# Eletromiografia.net
KiCad netlist of a schematic drawn in EAGLE
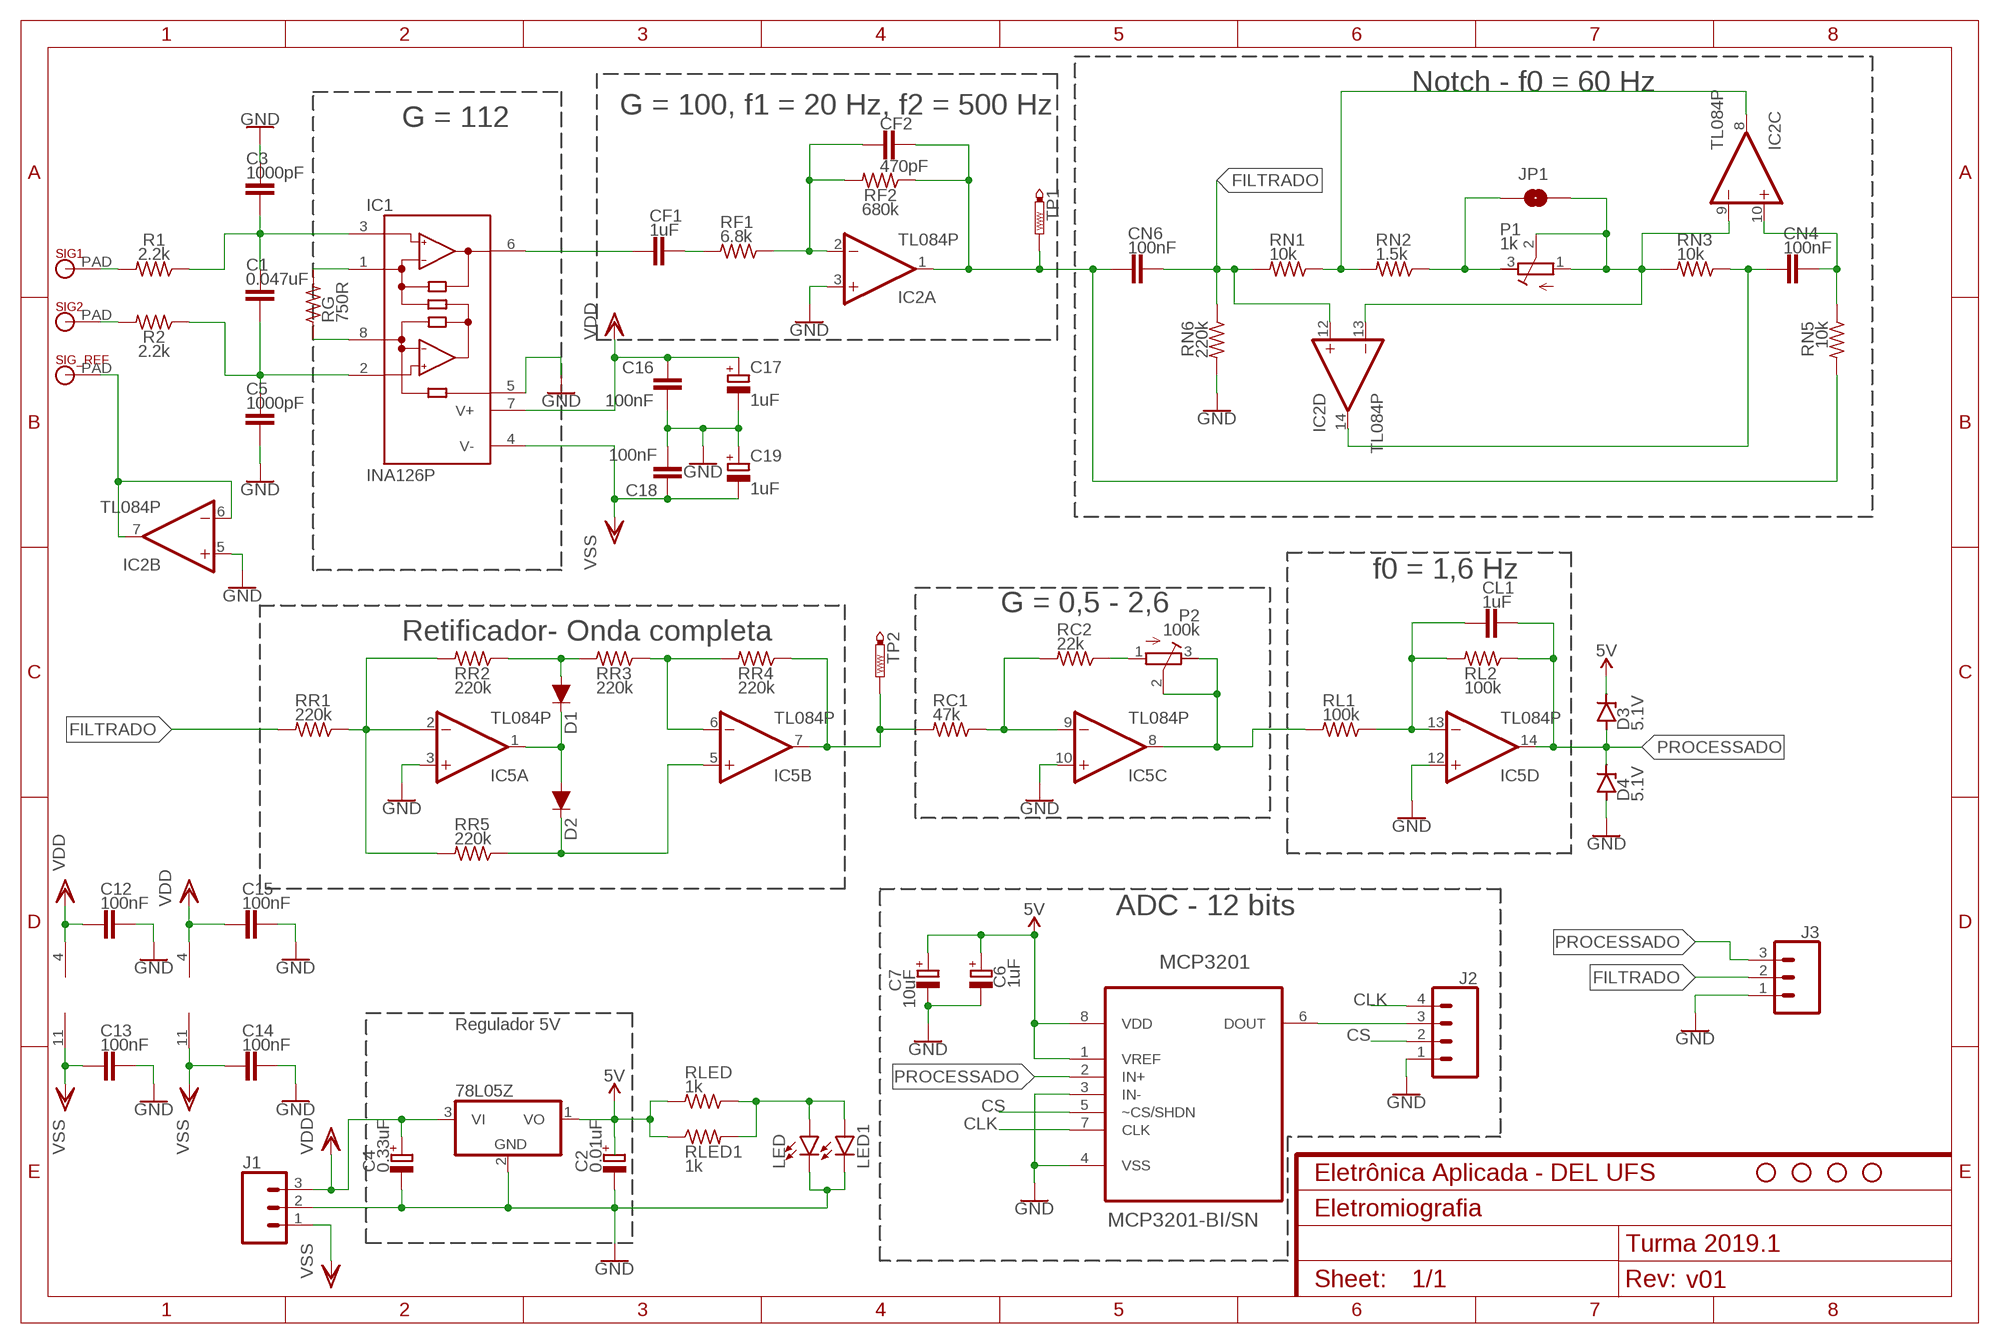
[diagram p0: schematic, sheet 1]

(export (version "E")
  (design (tool "Eeschema 10.0.6"))
  (components
    (comp (ref "C1")
      (value "0.047uF")
      (footprint "eagle-import:C025-025X050")
      (libsource (lib "eagle-import") (part "C-EU025-025X050"))
    )
    (comp (ref "C2")
      (value "0.01uF")
      (footprint "eagle-import:E2,5-6")
      (libsource (lib "eagle-import") (part "CPOL-EUE2.5-6"))
    )
    (comp (ref "C3")
      (value "1000pF")
      (footprint "eagle-import:C025-025X050")
      (libsource (lib "eagle-import") (part "C-EU025-025X050"))
    )
    (comp (ref "C4")
      (value "0.33uF")
      (footprint "eagle-import:E2,5-6")
      (libsource (lib "eagle-import") (part "CPOL-EUE2.5-6"))
    )
    (comp (ref "C5")
      (value "1000pF")
      (footprint "eagle-import:C025-025X050")
      (libsource (lib "eagle-import") (part "C-EU025-025X050"))
    )
    (comp (ref "C6")
      (value "1uF")
      (footprint "eagle-import:E2,5-6")
      (libsource (lib "eagle-import") (part "CPOL-EUE2.5-6"))
    )
    (comp (ref "C7")
      (value "10uF")
      (footprint "eagle-import:E2,5-6")
      (libsource (lib "eagle-import") (part "CPOL-EUE2.5-6"))
    )
    (comp (ref "C12")
      (value "100nF")
      (footprint "eagle-import:C025-025X050")
      (libsource (lib "eagle-import") (part "C-EU025-025X050"))
    )
    (comp (ref "C13")
      (value "100nF")
      (footprint "eagle-import:C025-025X050")
      (libsource (lib "eagle-import") (part "C-EU025-025X050"))
    )
    (comp (ref "C14")
      (value "100nF")
      (footprint "eagle-import:C025-025X050")
      (libsource (lib "eagle-import") (part "C-EU025-025X050"))
    )
    (comp (ref "C15")
      (value "100nF")
      (footprint "eagle-import:C025-025X050")
      (libsource (lib "eagle-import") (part "C-EU025-025X050"))
    )
    (comp (ref "C16")
      (value "100nF")
      (footprint "eagle-import:C025-025X050")
      (libsource (lib "eagle-import") (part "C-EU025-025X050"))
    )
    (comp (ref "C17")
      (value "1uF")
      (footprint "eagle-import:E2,5-6")
      (libsource (lib "eagle-import") (part "CPOL-EUE2.5-6"))
    )
    (comp (ref "C18")
      (value "100nF")
      (footprint "eagle-import:C025-025X050")
      (libsource (lib "eagle-import") (part "C-EU025-025X050"))
    )
    (comp (ref "C19")
      (value "1uF")
      (footprint "eagle-import:E2,5-6")
      (libsource (lib "eagle-import") (part "CPOL-EUE2.5-6"))
    )
    (comp (ref "CF1")
      (value "1uF")
      (footprint "eagle-import:C025-025X050")
      (libsource (lib "eagle-import") (part "C-EU025-025X050"))
    )
    (comp (ref "CF2")
      (value "470pF")
      (footprint "eagle-import:C025-025X050")
      (libsource (lib "eagle-import") (part "C-EU025-025X050"))
    )
    (comp (ref "CL1")
      (value "1uF")
      (footprint "eagle-import:C025-025X050")
      (libsource (lib "eagle-import") (part "C-EU025-025X050"))
    )
    (comp (ref "CN4")
      (value "100nF")
      (footprint "eagle-import:C025-025X050")
      (libsource (lib "eagle-import") (part "C-EU025-025X050"))
    )
    (comp (ref "CN6")
      (value "100nF")
      (footprint "eagle-import:C025-025X050")
      (libsource (lib "eagle-import") (part "C-EU025-025X050"))
    )
    (comp (ref "D1")
      (value "200mA/100V/1V")
      (footprint "eagle-import:DIODE-1N4148")
      (libsource (lib "eagle-import") (part "DIODE-1N4148"))
    )
    (comp (ref "D2")
      (value "200mA/100V/1V")
      (footprint "eagle-import:DIODE-1N4148")
      (libsource (lib "eagle-import") (part "DIODE-1N4148"))
    )
    (comp (ref "D3")
      (value "5.1V")
      (footprint "eagle-import:ZDIO-7.5")
      (libsource (lib "eagle-import") (part "ZENER-DIODEZD-7.5"))
    )
    (comp (ref "D4")
      (value "5.1V")
      (footprint "eagle-import:ZDIO-7.5")
      (libsource (lib "eagle-import") (part "ZENER-DIODEZD-7.5"))
    )
    (comp (ref "H1")
      (value "STAND-OFFTIGHT")
      (footprint "eagle-import:STAND-OFF-TIGHT")
      (libsource (lib "eagle-import") (part "STAND-OFFTIGHT"))
    )
    (comp (ref "H2")
      (value "STAND-OFFTIGHT")
      (footprint "eagle-import:STAND-OFF-TIGHT")
      (libsource (lib "eagle-import") (part "STAND-OFFTIGHT"))
    )
    (comp (ref "H3")
      (value "STAND-OFFTIGHT")
      (footprint "eagle-import:STAND-OFF-TIGHT")
      (libsource (lib "eagle-import") (part "STAND-OFFTIGHT"))
    )
    (comp (ref "H4")
      (value "STAND-OFFTIGHT")
      (footprint "eagle-import:STAND-OFF-TIGHT")
      (libsource (lib "eagle-import") (part "STAND-OFFTIGHT"))
    )
    (comp (ref "IC1")
      (value "INA126P")
      (footprint "eagle-import:DIL08")
      (fields (field (name "MF") "TEXAS INSTRUMENT CONNECTORS"))
      (libsource (lib "eagle-import") (part "INA126P"))
    )
    (comp (ref "IC2")
      (value "TL084P")
      (footprint "eagle-import:DIL14")
      (libsource (lib "eagle-import") (part "TL084P"))
    )
    (comp (ref "IC3")
      (value "78L05Z")
      (footprint "eagle-import:TO92")
      (libsource (lib "eagle-import") (part "78ZL05"))
    )
    (comp (ref "IC5")
      (value "TL084P")
      (footprint "eagle-import:DIL14")
      (libsource (lib "eagle-import") (part "TL084P"))
    )
    (comp (ref "J1")
      (value "CONN_03LONGPADS")
      (footprint "eagle-import:1X03_LONGPADS")
      (libsource (lib "eagle-import") (part "CONN_03LONGPADS"))
    )
    (comp (ref "J2")
      (value "CONN_041X04_NO_SILK")
      (footprint "eagle-import:1X04_NO_SILK")
      (libsource (lib "eagle-import") (part "CONN_041X04_NO_SILK"))
    )
    (comp (ref "J3")
      (value "CONN_031X03_NO_SILK")
      (footprint "eagle-import:1X03_NO_SILK")
      (libsource (lib "eagle-import") (part "CONN_031X03_NO_SILK"))
    )
    (comp (ref "JP1")
      (value "JUMPER-SMT_2_NO_NO-SILK_ROUND")
      (footprint "eagle-import:SMT-JUMPER_2_NO_NO-SILK_ROUND")
      (libsource (lib "eagle-import") (part "JUMPER-SMT_2_NO_NO-SILK_ROUND"))
    )
    (comp (ref "LED")
      (value "LED3MM")
      (footprint "eagle-import:LED_3MM")
      (libsource (lib "eagle-import") (part "LED3MM"))
    )
    (comp (ref "LED1")
      (value "LEDCHIP-LED0805")
      (footprint "eagle-import:CHIP-LED0805")
      (libsource (lib "eagle-import") (part "LEDCHIP-LED0805"))
    )
    (comp (ref "MCP3201")
      (value "MCP3201-BI/SN")
      (footprint "eagle-import:SOIC127P600X175-8N")
      (fields (field (name "MF") "Microchip"))
      (libsource (lib "eagle-import") (part "MCP3201-BI/SN"))
    )
    (comp (ref "P1")
      (value "1k")
      (footprint "eagle-import:RTRIM64W")
      (libsource (lib "eagle-import") (part "R-TRIMM64W"))
    )
    (comp (ref "P2")
      (value "100k")
      (footprint "eagle-import:RTRIM64W")
      (libsource (lib "eagle-import") (part "R-TRIMM64W"))
    )
    (comp (ref "R1")
      (value "2.2k")
      (footprint "eagle-import:0207_10")
      (libsource (lib "eagle-import") (part "R-US_0207/10"))
    )
    (comp (ref "R2")
      (value "2.2k")
      (footprint "eagle-import:0207_10")
      (libsource (lib "eagle-import") (part "R-US_0207/10"))
    )
    (comp (ref "RC1")
      (value "47k")
      (footprint "eagle-import:0207_10")
      (libsource (lib "eagle-import") (part "R-US_0207/10"))
    )
    (comp (ref "RC2")
      (value "22k")
      (footprint "eagle-import:0207_10")
      (libsource (lib "eagle-import") (part "R-US_0207/10"))
    )
    (comp (ref "RF1")
      (value "6.8k")
      (footprint "eagle-import:0207_10")
      (libsource (lib "eagle-import") (part "R-US_0207/10"))
    )
    (comp (ref "RF2")
      (value "680k")
      (footprint "eagle-import:0207_10")
      (libsource (lib "eagle-import") (part "R-US_0207/10"))
    )
    (comp (ref "RG")
      (value "750R")
      (footprint "eagle-import:0207_10")
      (libsource (lib "eagle-import") (part "R-US_0207/10"))
    )
    (comp (ref "RL1")
      (value "100k")
      (footprint "eagle-import:0207_10")
      (libsource (lib "eagle-import") (part "R-US_0207/10"))
    )
    (comp (ref "RL2")
      (value "100k")
      (footprint "eagle-import:0207_10")
      (libsource (lib "eagle-import") (part "R-US_0207/10"))
    )
    (comp (ref "RLED")
      (value "1k")
      (footprint "eagle-import:0207_10")
      (libsource (lib "eagle-import") (part "R-US_0207/10"))
    )
    (comp (ref "RLED1")
      (value "1k")
      (footprint "eagle-import:R0805")
      (libsource (lib "eagle-import") (part "R-US_R0805"))
    )
    (comp (ref "RN1")
      (value "10k")
      (footprint "eagle-import:0207_10")
      (libsource (lib "eagle-import") (part "R-US_0207/10"))
    )
    (comp (ref "RN2")
      (value "1.5k")
      (footprint "eagle-import:0207_10")
      (libsource (lib "eagle-import") (part "R-US_0207/10"))
    )
    (comp (ref "RN3")
      (value "10k")
      (footprint "eagle-import:0207_10")
      (libsource (lib "eagle-import") (part "R-US_0207/10"))
    )
    (comp (ref "RN5")
      (value "10k")
      (footprint "eagle-import:0207_10")
      (libsource (lib "eagle-import") (part "R-US_0207/10"))
    )
    (comp (ref "RN6")
      (value "220k")
      (footprint "eagle-import:0207_10")
      (libsource (lib "eagle-import") (part "R-US_0207/10"))
    )
    (comp (ref "RR1")
      (value "220k")
      (footprint "eagle-import:0207_10")
      (libsource (lib "eagle-import") (part "R-US_0207/10"))
    )
    (comp (ref "RR2")
      (value "220k")
      (footprint "eagle-import:0207_10")
      (libsource (lib "eagle-import") (part "R-US_0207/10"))
    )
    (comp (ref "RR3")
      (value "220k")
      (footprint "eagle-import:0207_10")
      (libsource (lib "eagle-import") (part "R-US_0207/10"))
    )
    (comp (ref "RR4")
      (value "220k")
      (footprint "eagle-import:0207_10")
      (libsource (lib "eagle-import") (part "R-US_0207/10"))
    )
    (comp (ref "RR5")
      (value "220k")
      (footprint "eagle-import:0207_10")
      (libsource (lib "eagle-import") (part "R-US_0207/10"))
    )
    (comp (ref "SIG1")
      (value "MICROBIT_PAD")
      (footprint "eagle-import:MICROBIT_PAD")
      (libsource (lib "eagle-import") (part "MICROBIT_PAD"))
    )
    (comp (ref "SIG2")
      (value "MICROBIT_PAD")
      (footprint "eagle-import:MICROBIT_PAD")
      (libsource (lib "eagle-import") (part "MICROBIT_PAD"))
    )
    (comp (ref "SIG_REF")
      (value "MICROBIT_PAD")
      (footprint "eagle-import:MICROBIT_PAD")
      (libsource (lib "eagle-import") (part "MICROBIT_PAD"))
    )
    (comp (ref "TP1")
      (value "PTR1B1,27")
      (footprint "eagle-import:B1,27")
      (libsource (lib "eagle-import") (part "PTR1B1,27"))
    )
    (comp (ref "TP2")
      (value "PTR1B1,27")
      (footprint "eagle-import:B1,27")
      (libsource (lib "eagle-import") (part "PTR1B1,27"))
    )
  )
  (nets
    (net (code "1") (name "/CLK") (class "Default")
      (node (ref "J2") (pin "4") (pinfunction "4_4") (pintype "passive"))
      (node (ref "MCP3201") (pin "7") (pinfunction "CLK_7") (pintype "input"))
    )
    (net (code "2") (name "/CS") (class "Default")
      (node (ref "J2") (pin "2") (pinfunction "2_2") (pintype "passive"))
      (node (ref "MCP3201") (pin "5") (pinfunction "~{CS/SHDN}_5") (pintype "input"))
    )
    (net (code "3") (name "5V") (class "Default")
      (node (ref "C2") (pin "+") (pinfunction "+_+") (pintype "passive"))
      (node (ref "C6") (pin "+") (pinfunction "+_+") (pintype "passive"))
      (node (ref "C7") (pin "+") (pinfunction "+_+") (pintype "passive"))
      (node (ref "D3") (pin "C") (pinfunction "C_C") (pintype "passive"))
      (node (ref "IC3") (pin "1") (pinfunction "VO_1") (pintype "passive"))
      (node (ref "MCP3201") (pin "1") (pinfunction "VREF_1") (pintype "input"))
      (node (ref "MCP3201") (pin "8") (pinfunction "VDD_8") (pintype "power_in"))
      (node (ref "RLED") (pin "2") (pinfunction "2_2") (pintype "passive"))
      (node (ref "RLED1") (pin "1") (pinfunction "1_1") (pintype "passive"))
    )
    (net (code "4") (name "FILTRADO") (class "Default")
      (node (ref "CN6") (pin "2") (pinfunction "2_2") (pintype "passive"))
      (node (ref "IC2") (pin "12") (pinfunction "+IN_12") (pintype "input"))
      (node (ref "J3") (pin "2") (pinfunction "2_2") (pintype "passive"))
      (node (ref "RN1") (pin "2") (pinfunction "2_2") (pintype "passive"))
      (node (ref "RN6") (pin "1") (pinfunction "1_1") (pintype "passive"))
      (node (ref "RR1") (pin "2") (pinfunction "2_2") (pintype "passive"))
    )
    (net (code "5") (name "GND") (class "Default")
      (node (ref "C12") (pin "2") (pinfunction "2_2") (pintype "passive"))
      (node (ref "C13") (pin "2") (pinfunction "2_2") (pintype "passive"))
      (node (ref "C14") (pin "2") (pinfunction "2_2") (pintype "passive"))
      (node (ref "C15") (pin "2") (pinfunction "2_2") (pintype "passive"))
      (node (ref "C16") (pin "1") (pinfunction "1_1") (pintype "passive"))
      (node (ref "C17") (pin "-") (pinfunction "-_-") (pintype "passive"))
      (node (ref "C18") (pin "2") (pinfunction "2_2") (pintype "passive"))
      (node (ref "C19") (pin "+") (pinfunction "+_+") (pintype "passive"))
      (node (ref "C2") (pin "-") (pinfunction "-_-") (pintype "passive"))
      (node (ref "C3") (pin "2") (pinfunction "2_2") (pintype "passive"))
      (node (ref "C4") (pin "-") (pinfunction "-_-") (pintype "passive"))
      (node (ref "C5") (pin "1") (pinfunction "1_1") (pintype "passive"))
      (node (ref "C6") (pin "-") (pinfunction "-_-") (pintype "passive"))
      (node (ref "C7") (pin "-") (pinfunction "-_-") (pintype "passive"))
      (node (ref "D4") (pin "A") (pinfunction "A_A") (pintype "passive"))
      (node (ref "IC1") (pin "5") (pinfunction "REF_5") (pintype "passive"))
      (node (ref "IC2") (pin "3") (pinfunction "+IN_3") (pintype "input"))
      (node (ref "IC2") (pin "5") (pinfunction "+IN_5") (pintype "input"))
      (node (ref "IC3") (pin "2") (pinfunction "GND_2") (pintype "passive"))
      (node (ref "IC5") (pin "10") (pinfunction "+IN_10") (pintype "input"))
      (node (ref "IC5") (pin "12") (pinfunction "+IN_12") (pintype "input"))
      (node (ref "IC5") (pin "3") (pinfunction "+IN_3") (pintype "input"))
      (node (ref "J1") (pin "2") (pinfunction "2_2") (pintype "passive"))
      (node (ref "J2") (pin "1") (pinfunction "1_1") (pintype "passive"))
      (node (ref "J3") (pin "1") (pinfunction "1_1") (pintype "passive"))
      (node (ref "LED") (pin "K") (pinfunction "C_K") (pintype "passive"))
      (node (ref "LED1") (pin "C") (pinfunction "C_C") (pintype "passive"))
      (node (ref "MCP3201") (pin "3") (pinfunction "IN-_3") (pintype "input"))
      (node (ref "MCP3201") (pin "4") (pinfunction "VSS_4") (pintype "power_in"))
      (node (ref "RN6") (pin "2") (pinfunction "2_2") (pintype "passive"))
    )
    (net (code "6") (name "Net-(CF1-Pad2)") (class "Default")
      (node (ref "CF1") (pin "2") (pinfunction "2_2") (pintype "passive"))
      (node (ref "RF1") (pin "2") (pinfunction "2_2") (pintype "passive"))
    )
    (net (code "7") (name "Net-(D1-PadA)") (class "Default")
      (node (ref "D1") (pin "A") (pinfunction "A_A") (pintype "passive"))
      (node (ref "RR2") (pin "1") (pinfunction "1_1") (pintype "passive"))
      (node (ref "RR3") (pin "2") (pinfunction "2_2") (pintype "passive"))
    )
    (net (code "8") (name "Net-(IC1-+IN)") (class "Default")
      (node (ref "C1") (pin "2") (pinfunction "2_2") (pintype "passive"))
      (node (ref "C3") (pin "1") (pinfunction "1_1") (pintype "passive"))
      (node (ref "IC1") (pin "3") (pinfunction "+IN_3") (pintype "input"))
      (node (ref "R1") (pin "1") (pinfunction "1_1") (pintype "passive"))
    )
    (net (code "9") (name "Net-(IC1--IN)") (class "Default")
      (node (ref "C1") (pin "1") (pinfunction "1_1") (pintype "passive"))
      (node (ref "C5") (pin "2") (pinfunction "2_2") (pintype "passive"))
      (node (ref "IC1") (pin "2") (pinfunction "-IN_2") (pintype "input"))
      (node (ref "R2") (pin "1") (pinfunction "1_1") (pintype "passive"))
    )
    (net (code "10") (name "Net-(IC1-OUT)") (class "Default")
      (node (ref "CF1") (pin "1") (pinfunction "1_1") (pintype "passive"))
      (node (ref "IC1") (pin "6") (pinfunction "OUT_6") (pintype "output"))
    )
    (net (code "11") (name "Net-(IC1-RG-Pad1)") (class "Default")
      (node (ref "IC1") (pin "1") (pinfunction "RG_1") (pintype "passive"))
      (node (ref "RG") (pin "2") (pinfunction "2_2") (pintype "passive"))
    )
    (net (code "12") (name "Net-(IC1-RG-Pad8)") (class "Default")
      (node (ref "IC1") (pin "8") (pinfunction "RG_8") (pintype "passive"))
      (node (ref "RG") (pin "1") (pinfunction "1_1") (pintype "passive"))
    )
    (net (code "13") (name "Net-(IC2A--IN)") (class "Default")
      (node (ref "CF2") (pin "1") (pinfunction "1_1") (pintype "passive"))
      (node (ref "IC2") (pin "2") (pinfunction "-IN_2") (pintype "input"))
      (node (ref "RF1") (pin "1") (pinfunction "1_1") (pintype "passive"))
      (node (ref "RF2") (pin "2") (pinfunction "2_2") (pintype "passive"))
    )
    (net (code "14") (name "Net-(IC2A-OUT)") (class "Default")
      (node (ref "CF2") (pin "2") (pinfunction "2_2") (pintype "passive"))
      (node (ref "CN6") (pin "1") (pinfunction "1_1") (pintype "passive"))
      (node (ref "IC2") (pin "1") (pinfunction "OUT_1") (pintype "output"))
      (node (ref "RF2") (pin "1") (pinfunction "1_1") (pintype "passive"))
      (node (ref "RN5") (pin "2") (pinfunction "2_2") (pintype "passive"))
      (node (ref "TP1") (pin "TP") (pinfunction "TP_TP") (pintype "input"))
    )
    (net (code "15") (name "Net-(IC2B--IN)") (class "Default")
      (node (ref "IC2") (pin "6") (pinfunction "-IN_6") (pintype "input"))
      (node (ref "IC2") (pin "7") (pinfunction "OUT_7") (pintype "output"))
      (node (ref "SIG_REF") (pin "PAD") (pinfunction "P$1_PAD") (pintype "bidirectional"))
    )
    (net (code "16") (name "Net-(IC2C-+IN)") (class "Default")
      (node (ref "CN4") (pin "2") (pinfunction "2_2") (pintype "passive"))
      (node (ref "IC2") (pin "10") (pinfunction "+IN_10") (pintype "input"))
      (node (ref "RN5") (pin "1") (pinfunction "1_1") (pintype "passive"))
    )
    (net (code "17") (name "Net-(IC2C--IN)") (class "Default")
      (node (ref "IC2") (pin "13") (pinfunction "-IN_13") (pintype "input"))
      (node (ref "IC2") (pin "9") (pinfunction "-IN_9") (pintype "input"))
      (node (ref "JP1") (pin "2") (pinfunction "2_2") (pintype "passive"))
      (node (ref "P1") (pin "1") (pinfunction "A_1") (pintype "passive"))
      (node (ref "P1") (pin "2") (pinfunction "S_2") (pintype "passive"))
      (node (ref "RN3") (pin "2") (pinfunction "2_2") (pintype "passive"))
    )
    (net (code "18") (name "Net-(IC2C-OUT)") (class "Default")
      (node (ref "IC2") (pin "8") (pinfunction "OUT_8") (pintype "output"))
      (node (ref "RN1") (pin "1") (pinfunction "1_1") (pintype "passive"))
      (node (ref "RN2") (pin "2") (pinfunction "2_2") (pintype "passive"))
    )
    (net (code "19") (name "Net-(IC2D-OUT)") (class "Default")
      (node (ref "CN4") (pin "1") (pinfunction "1_1") (pintype "passive"))
      (node (ref "IC2") (pin "14") (pinfunction "OUT_14") (pintype "output"))
      (node (ref "RN3") (pin "1") (pinfunction "1_1") (pintype "passive"))
    )
    (net (code "20") (name "Net-(IC5A--IN)") (class "Default")
      (node (ref "IC5") (pin "2") (pinfunction "-IN_2") (pintype "input"))
      (node (ref "RR1") (pin "1") (pinfunction "1_1") (pintype "passive"))
      (node (ref "RR2") (pin "2") (pinfunction "2_2") (pintype "passive"))
      (node (ref "RR5") (pin "2") (pinfunction "2_2") (pintype "passive"))
    )
    (net (code "21") (name "Net-(IC5A-OUT)") (class "Default")
      (node (ref "D1") (pin "C") (pinfunction "C_C") (pintype "passive"))
      (node (ref "D2") (pin "A") (pinfunction "A_A") (pintype "passive"))
      (node (ref "IC5") (pin "1") (pinfunction "OUT_1") (pintype "output"))
    )
    (net (code "22") (name "Net-(IC5B-+IN)") (class "Default")
      (node (ref "D2") (pin "C") (pinfunction "C_C") (pintype "passive"))
      (node (ref "IC5") (pin "5") (pinfunction "+IN_5") (pintype "input"))
      (node (ref "RR5") (pin "1") (pinfunction "1_1") (pintype "passive"))
    )
    (net (code "23") (name "Net-(IC5B--IN)") (class "Default")
      (node (ref "IC5") (pin "6") (pinfunction "-IN_6") (pintype "input"))
      (node (ref "RR3") (pin "1") (pinfunction "1_1") (pintype "passive"))
      (node (ref "RR4") (pin "2") (pinfunction "2_2") (pintype "passive"))
    )
    (net (code "24") (name "Net-(IC5B-OUT)") (class "Default")
      (node (ref "IC5") (pin "7") (pinfunction "OUT_7") (pintype "output"))
      (node (ref "RC1") (pin "2") (pinfunction "2_2") (pintype "passive"))
      (node (ref "RR4") (pin "1") (pinfunction "1_1") (pintype "passive"))
      (node (ref "TP2") (pin "TP") (pinfunction "TP_TP") (pintype "input"))
    )
    (net (code "25") (name "Net-(IC5C--IN)") (class "Default")
      (node (ref "IC5") (pin "9") (pinfunction "-IN_9") (pintype "input"))
      (node (ref "RC1") (pin "1") (pinfunction "1_1") (pintype "passive"))
      (node (ref "RC2") (pin "2") (pinfunction "2_2") (pintype "passive"))
    )
    (net (code "26") (name "Net-(IC5C-OUT)") (class "Default")
      (node (ref "IC5") (pin "8") (pinfunction "OUT_8") (pintype "output"))
      (node (ref "P2") (pin "2") (pinfunction "S_2") (pintype "passive"))
      (node (ref "P2") (pin "3") (pinfunction "E_3") (pintype "passive"))
      (node (ref "RL1") (pin "2") (pinfunction "2_2") (pintype "passive"))
    )
    (net (code "27") (name "Net-(IC5D--IN)") (class "Default")
      (node (ref "CL1") (pin "1") (pinfunction "1_1") (pintype "passive"))
      (node (ref "IC5") (pin "13") (pinfunction "-IN_13") (pintype "input"))
      (node (ref "RL1") (pin "1") (pinfunction "1_1") (pintype "passive"))
      (node (ref "RL2") (pin "2") (pinfunction "2_2") (pintype "passive"))
    )
    (net (code "28") (name "Net-(LED-PadA)") (class "Default")
      (node (ref "LED") (pin "A") (pinfunction "A_A") (pintype "passive"))
      (node (ref "LED1") (pin "A") (pinfunction "A_A") (pintype "passive"))
      (node (ref "RLED") (pin "1") (pinfunction "1_1") (pintype "passive"))
      (node (ref "RLED1") (pin "2") (pinfunction "2_2") (pintype "passive"))
    )
    (net (code "29") (name "Net-(MCP3201-DOUT)") (class "Default")
      (node (ref "J2") (pin "3") (pinfunction "3_3") (pintype "passive"))
      (node (ref "MCP3201") (pin "6") (pinfunction "DOUT_6") (pintype "output"))
    )
    (net (code "30") (name "Net-(P1-E)") (class "Default")
      (node (ref "JP1") (pin "1") (pinfunction "1_1") (pintype "passive"))
      (node (ref "P1") (pin "3") (pinfunction "E_3") (pintype "passive"))
      (node (ref "RN2") (pin "1") (pinfunction "1_1") (pintype "passive"))
    )
    (net (code "31") (name "Net-(P2-A)") (class "Default")
      (node (ref "P2") (pin "1") (pinfunction "A_1") (pintype "passive"))
      (node (ref "RC2") (pin "1") (pinfunction "1_1") (pintype "passive"))
    )
    (net (code "32") (name "Net-(SIG1-P$1)") (class "Default")
      (node (ref "R1") (pin "2") (pinfunction "2_2") (pintype "passive"))
      (node (ref "SIG1") (pin "PAD") (pinfunction "P$1_PAD") (pintype "bidirectional"))
    )
    (net (code "33") (name "Net-(SIG2-P$1)") (class "Default")
      (node (ref "R2") (pin "2") (pinfunction "2_2") (pintype "passive"))
      (node (ref "SIG2") (pin "PAD") (pinfunction "P$1_PAD") (pintype "bidirectional"))
    )
    (net (code "34") (name "PROCESSADO") (class "Default")
      (node (ref "CL1") (pin "2") (pinfunction "2_2") (pintype "passive"))
      (node (ref "D3") (pin "A") (pinfunction "A_A") (pintype "passive"))
      (node (ref "D4") (pin "C") (pinfunction "C_C") (pintype "passive"))
      (node (ref "IC5") (pin "14") (pinfunction "OUT_14") (pintype "output"))
      (node (ref "J3") (pin "3") (pinfunction "3_3") (pintype "passive"))
      (node (ref "MCP3201") (pin "2") (pinfunction "IN+_2") (pintype "input"))
      (node (ref "RL2") (pin "1") (pinfunction "1_1") (pintype "passive"))
    )
    (net (code "35") (name "VDD") (class "Default")
      (node (ref "C12") (pin "1") (pinfunction "1_1") (pintype "passive"))
      (node (ref "C15") (pin "1") (pinfunction "1_1") (pintype "passive"))
      (node (ref "C16") (pin "2") (pinfunction "2_2") (pintype "passive"))
      (node (ref "C17") (pin "+") (pinfunction "+_+") (pintype "passive"))
      (node (ref "C4") (pin "+") (pinfunction "+_+") (pintype "passive"))
      (node (ref "IC1") (pin "7") (pinfunction "V+_7") (pintype "power_in"))
      (node (ref "IC2") (pin "4") (pinfunction "V+_4") (pintype "power_in"))
      (node (ref "IC3") (pin "3") (pinfunction "VI_3") (pintype "input"))
      (node (ref "IC5") (pin "4") (pinfunction "V+_4") (pintype "power_in"))
      (node (ref "J1") (pin "3") (pinfunction "3_3") (pintype "passive"))
    )
    (net (code "36") (name "VSS") (class "Default")
      (node (ref "C13") (pin "1") (pinfunction "1_1") (pintype "passive"))
      (node (ref "C14") (pin "1") (pinfunction "1_1") (pintype "passive"))
      (node (ref "C18") (pin "1") (pinfunction "1_1") (pintype "passive"))
      (node (ref "C19") (pin "-") (pinfunction "-_-") (pintype "passive"))
      (node (ref "IC1") (pin "4") (pinfunction "V-_4") (pintype "power_in"))
      (node (ref "IC2") (pin "11") (pinfunction "V-_11") (pintype "power_in"))
      (node (ref "IC5") (pin "11") (pinfunction "V-_11") (pintype "power_in"))
      (node (ref "J1") (pin "1") (pinfunction "1_1") (pintype "passive"))
    )
  )
)
